# Bike_Light.net
KiCad netlist of a schematic drawn in EAGLE
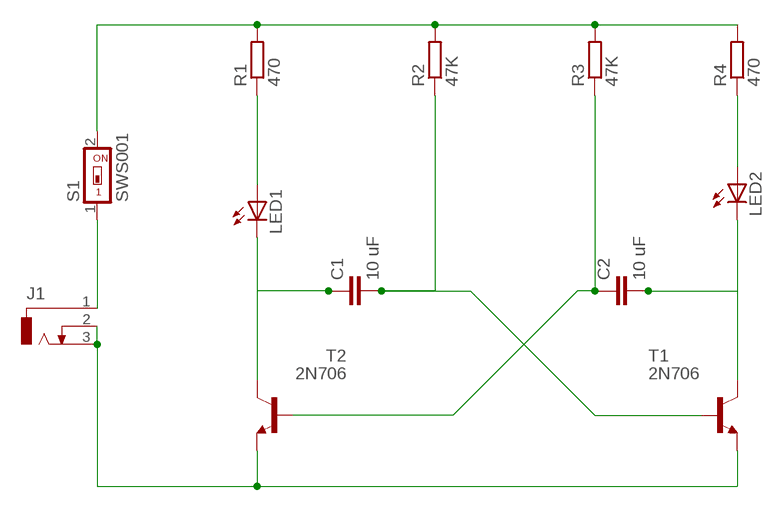
[diagram p0: schematic, sheet 1]

(export (version "E")
  (design (tool "Eeschema 10.0.6"))
  (components
    (comp (ref "C1")
      (value "10 uF")
      (footprint "eagle-import:C2.5-3")
      (libsource (lib "eagle-import") (part "C2,5-3"))
    )
    (comp (ref "C2")
      (value "10 uF")
      (footprint "eagle-import:C2.5-3")
      (libsource (lib "eagle-import") (part "C2,5-3"))
    )
    (comp (ref "J1")
      (value "DCJ0303")
      (footprint "eagle-import:DCJ0303")
      (libsource (lib "eagle-import") (part "DCJ0303"))
    )
    (comp (ref "LED1")
      (value "LED5MM")
      (footprint "eagle-import:LED5MM")
      (libsource (lib "eagle-import") (part "LED5MM"))
    )
    (comp (ref "LED2")
      (value "LED5MM")
      (footprint "eagle-import:LED5MM")
      (libsource (lib "eagle-import") (part "LED5MM"))
    )
    (comp (ref "R1")
      (value "470")
      (footprint "eagle-import:0207_10")
      (libsource (lib "eagle-import") (part "R-EU_0207/10"))
    )
    (comp (ref "R2")
      (value "47K")
      (footprint "eagle-import:0207_10")
      (libsource (lib "eagle-import") (part "R-EU_0207/10"))
    )
    (comp (ref "R3")
      (value "47K")
      (footprint "eagle-import:0207_10")
      (libsource (lib "eagle-import") (part "R-EU_0207/10"))
    )
    (comp (ref "R4")
      (value "470")
      (footprint "eagle-import:0207_10")
      (libsource (lib "eagle-import") (part "R-EU_0207/10"))
    )
    (comp (ref "S1")
      (value "SWS001")
      (footprint "eagle-import:SMS-001")
      (libsource (lib "eagle-import") (part "SWS001"))
    )
    (comp (ref "T1")
      (value "2N706")
      (footprint "eagle-import:TO18")
      (libsource (lib "eagle-import") (part "2N706"))
    )
    (comp (ref "T2")
      (value "2N706")
      (footprint "eagle-import:TO18")
      (libsource (lib "eagle-import") (part "2N706"))
    )
  )
  (nets
    (net (code "1") (name "Net-(J1-Pad1)") (class "Default")
      (node (ref "J1") (pin "1") (pinfunction "1_1") (pintype "passive"))
      (node (ref "S1") (pin "1") (pinfunction "1_1") (pintype "passive"))
    )
    (net (code "2") (name "Net-(LED1-C)") (class "Default")
      (node (ref "C1") (pin "1") (pinfunction "1_1") (pintype "passive"))
      (node (ref "LED1") (pin "K") (pinfunction "C_K") (pintype "passive"))
      (node (ref "T2") (pin "3") (pinfunction "C_3") (pintype "passive"))
    )
    (net (code "3") (name "Net-(LED1-PadA)") (class "Default")
      (node (ref "LED1") (pin "A") (pinfunction "A_A") (pintype "passive"))
      (node (ref "R1") (pin "1") (pinfunction "1_1") (pintype "passive"))
    )
    (net (code "4") (name "Net-(LED2-C)") (class "Default")
      (node (ref "C2") (pin "2") (pinfunction "2_2") (pintype "passive"))
      (node (ref "LED2") (pin "K") (pinfunction "C_K") (pintype "passive"))
      (node (ref "T1") (pin "3") (pinfunction "C_3") (pintype "passive"))
    )
    (net (code "5") (name "Net-(LED2-PadA)") (class "Default")
      (node (ref "LED2") (pin "A") (pinfunction "A_A") (pintype "passive"))
      (node (ref "R4") (pin "1") (pinfunction "1_1") (pintype "passive"))
    )
    (net (code "6") (name "Net-(R1-Pad2)") (class "Default")
      (node (ref "R1") (pin "2") (pinfunction "2_2") (pintype "passive"))
      (node (ref "R2") (pin "2") (pinfunction "2_2") (pintype "passive"))
      (node (ref "R3") (pin "2") (pinfunction "2_2") (pintype "passive"))
      (node (ref "R4") (pin "2") (pinfunction "2_2") (pintype "passive"))
      (node (ref "S1") (pin "2") (pinfunction "2_2") (pintype "passive"))
    )
    (net (code "7") (name "Net-(T1-B)") (class "Default")
      (node (ref "C1") (pin "2") (pinfunction "2_2") (pintype "passive"))
      (node (ref "R2") (pin "1") (pinfunction "1_1") (pintype "passive"))
      (node (ref "T1") (pin "2") (pinfunction "B_2") (pintype "passive"))
    )
    (net (code "8") (name "Net-(T1-E)") (class "Default")
      (node (ref "J1") (pin "2") (pinfunction "2_2") (pintype "passive"))
      (node (ref "J1") (pin "3") (pinfunction "3_3") (pintype "passive"))
      (node (ref "T1") (pin "1") (pinfunction "E_1") (pintype "passive"))
      (node (ref "T2") (pin "1") (pinfunction "E_1") (pintype "passive"))
    )
    (net (code "9") (name "Net-(T2-B)") (class "Default")
      (node (ref "C2") (pin "1") (pinfunction "1_1") (pintype "passive"))
      (node (ref "R3") (pin "1") (pinfunction "1_1") (pintype "passive"))
      (node (ref "T2") (pin "2") (pinfunction "B_2") (pintype "passive"))
    )
  )
)
